# TLV62569.net
KiCad netlist of a schematic drawn in Altium Designer
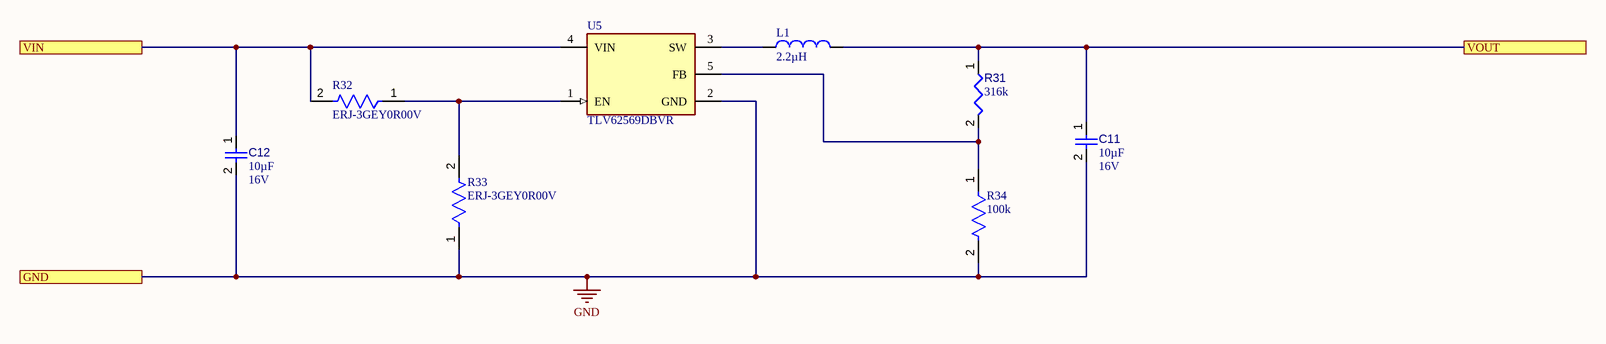
[diagram p0: TLV62569.SchDoc]

(export (version "E")
  (design (tool "Eeschema 10.0.6"))
  (components
    (comp (ref "C11")
      (value "10µF")
      (footprint "CAPC1608X09N")
      (fields (field (name "VOLTAGE RATING") "16V") (field (name "Comment") "CL10A106MO8NQNC"))
      (libsource (lib "Global Health Labs, Inc") (part "CAP-NP-2"))
    )
    (comp (ref "C12")
      (value "10µF")
      (footprint "CAPC1608X09N")
      (fields (field (name "VOLTAGE RATING") "16V") (field (name "Comment") "CL10A106MO8NQNC"))
      (libsource (lib "Global Health Labs, Inc") (part "CAP-NP-2"))
    )
    (comp (ref "L1")
      (value "2.2µH")
      (footprint "INDC5050X40N")
      (description "Shielded wirewound inductor, 2.2uH, 20%, 3.95A, 17 mohm DCR")
      (fields (field (name "TOLERANCE") "20%") (field (name "Comment") "CMLW5040S2R2MST"))
      (libsource (lib "Global Health Labs, Inc") (part "IND-2"))
    )
    (comp (ref "R31")
      (value "316k")
      (footprint "RESC0402(1005)_L")
      (description "Chip Resistor, 316 kOhms, +/-1 %, 63 mW, -55 to 155 degC, 0402")
      (fields (field (name "POWER") "63mW") (field (name "TOLERANCE") "1%"))
      (libsource (lib "Global Health Labs, Inc") (part "RES-2"))
    )
    (comp (ref "R32")
      (value "ERJ-3GEY0R00V")
      (footprint "FP-ERJ-3GEY0R00V-MFG")
      (description "0 Ohms Jumper 0.1W, 1/10W Chip Resistor 0603 (1608 Metric) Automotive AEC-Q200 Thick Film")
      (fields (field (name "TOLERANCE") "5%"))
      (libsource (lib "Altium Content Vault") (part "1029c3af85768c4190bb7ad29bc67b5"))
    )
    (comp (ref "R33")
      (value "ERJ-3GEY0R00V")
      (footprint "FP-ERJ-3GEY0R00V-MFG")
      (description "0 Ohms Jumper 0.1W, 1/10W Chip Resistor 0603 (1608 Metric) Automotive AEC-Q200 Thick Film")
      (fields (field (name "TOLERANCE") "5%"))
      (libsource (lib "Altium Content Vault") (part "1029c3af85768c4190bb7ad29bc67b5"))
    )
    (comp (ref "R34")
      (value "CRCW0402100KFKED")
      (footprint "FP-CRCW0402-e3-IPC_C")
      (description "RES Thick Film, 100kΩ, 1%, 0.063W, 100ppm/°C, 0402")
      (fields (field (name "RESISTANCE") "100k") (field (name "TOLERANCE") "1%"))
      (libsource (lib "Altium Content Vault") (part "1029c3af85768c4190bb7ad29bc67b5"))
    )
    (comp (ref "U5")
      (value "TLV62569DBVR")
      (footprint "FP-DBV0005A-IPC_B")
      (description "Switching Regulator, 2A, 1500kHz Switching Freq-Max, PDSO5")
      (libsource (lib "Global Health Labs, Inc") (part "f8671745ee5fb9a493b385c735b730b"))
    )
  )
  (nets
    (net (code "1") (name "/VIN") (class "Default")
      (node (ref "C12") (pin "1") (pinfunction "1_1") (pintype "passive"))
      (node (ref "R32") (pin "2") (pinfunction "2_2") (pintype "passive"))
      (node (ref "U5") (pin "4") (pinfunction "VIN_4") (pintype "power_in"))
    )
    (net (code "2") (name "/VOUT") (class "Default")
      (node (ref "C11") (pin "1") (pinfunction "1_1") (pintype "passive"))
      (node (ref "L1") (pin "2") (pinfunction "2_2") (pintype "passive"))
      (node (ref "R31") (pin "1") (pinfunction "1_1") (pintype "passive"))
    )
    (net (code "3") (name "GND") (class "Default")
      (node (ref "C11") (pin "2") (pinfunction "2_2") (pintype "passive"))
      (node (ref "C12") (pin "2") (pinfunction "2_2") (pintype "passive"))
      (node (ref "R33") (pin "1") (pinfunction "1_1") (pintype "passive"))
      (node (ref "R34") (pin "2") (pinfunction "2_2") (pintype "passive"))
      (node (ref "U5") (pin "2") (pinfunction "GND_2") (pintype "power_in"))
    )
    (net (code "4") (name "Net-(U5-EN)") (class "Default")
      (node (ref "R32") (pin "1") (pinfunction "1_1") (pintype "passive"))
      (node (ref "R33") (pin "2") (pinfunction "2_2") (pintype "passive"))
      (node (ref "U5") (pin "1") (pinfunction "EN_1") (pintype "input"))
    )
    (net (code "5") (name "Net-(U5-FB)") (class "Default")
      (node (ref "R31") (pin "2") (pinfunction "2_2") (pintype "passive"))
      (node (ref "R34") (pin "1") (pinfunction "1_1") (pintype "passive"))
      (node (ref "U5") (pin "5") (pinfunction "FB_5") (pintype "passive"))
    )
    (net (code "6") (name "Net-(U5-SW)") (class "Default")
      (node (ref "L1") (pin "1") (pinfunction "1_1") (pintype "passive"))
      (node (ref "U5") (pin "3") (pinfunction "SW_3") (pintype "power_in"))
    )
  )
)
